# DC_DC.net
KiCad netlist of a schematic drawn in Altium Designer
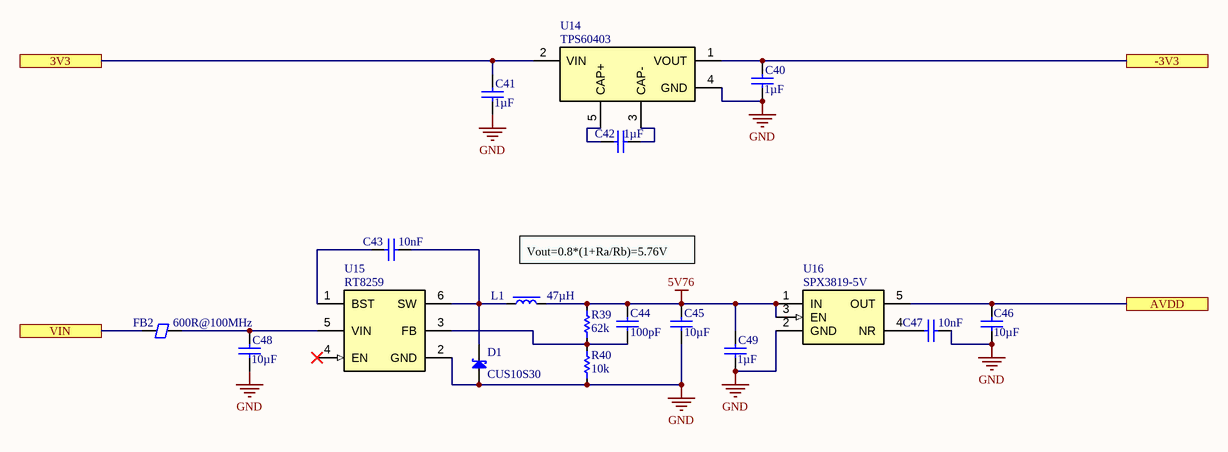
[diagram p0: DC DC.SchDoc]

(export (version "E")
  (design (tool "Eeschema 10.0.6"))
  (components
    (comp (ref "C40")
      (value "1µF")
      (footprint "CAP_CHIP_0603")
      (description "0603 Multilayer Ceramic Capacitors MLCC")
      (fields (field (name "PARTNUMBER") "CL10A105KB8NNNC") (field (name "TOLERANCE") "10%"))
      (libsource (lib "Sainsbury Wellcome Centre") (part "Cap"))
    )
    (comp (ref "C41")
      (value "1µF")
      (footprint "CAP_CHIP_0603")
      (description "0603 Multilayer Ceramic Capacitors MLCC")
      (fields (field (name "PARTNUMBER") "CL10A105KB8NNNC") (field (name "TOLERANCE") "10%"))
      (libsource (lib "Sainsbury Wellcome Centre") (part "Cap"))
    )
    (comp (ref "C42")
      (value "1µF")
      (footprint "CAP_CHIP_0603")
      (description "0603 Multilayer Ceramic Capacitors MLCC")
      (fields (field (name "PARTNUMBER") "CL10A105KB8NNNC") (field (name "TOLERANCE") "10%"))
      (libsource (lib "Sainsbury Wellcome Centre") (part "Cap"))
    )
    (comp (ref "C43")
      (value "10nF")
      (footprint "CAP_CHIP_0603")
      (description "0603 Multilayer Ceramic Capacitors MLCC")
      (fields (field (name "PARTNUMBER") "0603B103K500NT") (field (name "TOLERANCE") "10%"))
      (libsource (lib "Sainsbury Wellcome Centre") (part "Cap"))
    )
    (comp (ref "C44")
      (value "100pF")
      (footprint "CAP_CHIP_0603")
      (description "0603 Multilayer Ceramic Capacitors MLCC")
      (fields (field (name "TOLERANCE") "5%") (field (name "PARTNUMBER") "CL10C101JB8NNNC"))
      (libsource (lib "Sainsbury Wellcome Centre") (part "Cap"))
    )
    (comp (ref "C45")
      (value "10µF")
      (footprint "CAP_CHIP_0603")
      (fields
        (field (name "PARTNUMBER") "GRM188R6YA106MA73D")
        (field (name "TOLERANCE") "20%")
        (field (name "Comment") "C0603-10uF-35V")
      )
      (libsource (lib "Sainsbury Wellcome Centre") (part "Cap"))
    )
    (comp (ref "C46")
      (value "10µF")
      (footprint "CAP_CHIP_0603")
      (description "0603 Multilayer Ceramic Capacitors MLCC")
      (fields (field (name "PARTNUMBER") "CL10A106MA8NRNC") (field (name "TOLERANCE") "20%"))
      (libsource (lib "Sainsbury Wellcome Centre") (part "Cap"))
    )
    (comp (ref "C47")
      (value "10nF")
      (footprint "CAP_CHIP_0603")
      (description "0603 Multilayer Ceramic Capacitors MLCC")
      (fields (field (name "PARTNUMBER") "0603B103K500NT") (field (name "TOLERANCE") "10%"))
      (libsource (lib "Sainsbury Wellcome Centre") (part "Cap"))
    )
    (comp (ref "C48")
      (value "10µF")
      (footprint "CAP_CHIP_0603")
      (fields
        (field (name "PARTNUMBER") "GRM188R6YA106MA73D")
        (field (name "TOLERANCE") "20%")
        (field (name "Comment") "C0603-10uF-35V")
      )
      (libsource (lib "Sainsbury Wellcome Centre") (part "Cap"))
    )
    (comp (ref "C49")
      (value "1µF")
      (footprint "CAP_CHIP_0603")
      (description "0603 Multilayer Ceramic Capacitors MLCC")
      (fields (field (name "PARTNUMBER") "CL10A105KB8NNNC") (field (name "TOLERANCE") "10%"))
      (libsource (lib "Sainsbury Wellcome Centre") (part "Cap"))
    )
    (comp (ref "D1")
      (value "CUS10S30")
      (footprint "SOD323")
      (description "Rectifier Diode, Schottky, 1 Phase, 1 Element, 1A, 30V V(RRM), Silicon")
      (fields (field (name "PARTNUMBER") "CUS10S30,H3F"))
      (libsource (lib "Sainsbury Wellcome Centre") (part "Diode-Schottky"))
    )
    (comp (ref "FB2")
      (value "600R@100MHz")
      (footprint "FB_CHIP_0805")
      (description "Ferrite Chip, 1 Function(s), 0.5A, 2 Pin(s)")
      (fields (field (name "PARTNUMBER") "GZ2012D601TF") (field (name "Comment") "FB0805-600R-0.5A"))
      (libsource (lib "Sainsbury Wellcome Centre") (part "Bead"))
    )
    (comp (ref "L1")
      (value "47µH")
      (footprint "IND_PWR_1210")
      (description "Inductor Power Chip Shielded Wirewound 47uH 20% 1MHz Ferrite 0.5A 0.9Ohm DCR 1210 Automotive T/R")
      (fields (field (name "TOLERANCE") "20%") (field (name "PARTNUMBER") "LQW32FT470M0HL"))
      (libsource (lib "Sainsbury Wellcome Centre") (part "Inductor"))
    )
    (comp (ref "R39")
      (value "62k")
      (footprint "RES_CHIP_0603")
      (description "100mW Thick Film Resistors 75V ±100ppm/℃ ±1% 0603 Chip Resistor")
      (fields (field (name "TOLERANCE") "1%") (field (name "PARTNUMBER") "0603WAF6202T5E"))
      (libsource (lib "Sainsbury Wellcome Centre") (part "Res"))
    )
    (comp (ref "R40")
      (value "10k")
      (footprint "RES_CHIP_0603")
      (description "100mW Thick Film Resistors 75V ±100ppm/℃ ±1% 0603 Chip Resistor")
      (fields (field (name "PARTNUMBER") "0603WAF1002T5E") (field (name "TOLERANCE") "1%"))
      (libsource (lib "Sainsbury Wellcome Centre") (part "Res"))
    )
    (comp (ref "U14")
      (value "TPS60403")
      (footprint "SOT23-5")
      (description "60mA Charge Pump Voltage Inverter with Fixed 250kHz Operation 5-SOT-23 -40 to 85")
      (fields (field (name "PARTNUMBER") "TPS60403DBVR"))
      (libsource (lib "Sainsbury Wellcome Centre") (part "TPS60403"))
    )
    (comp (ref "U15")
      (value "RT8259")
      (footprint "SOT23-6")
      (description "Step-down type Adjustable 800mV~15V 1.2A 4.5V~24V Switching Regulator/Controller")
      (fields (field (name "PARTNUMBER") "RT8259GJ6"))
      (libsource (lib "Sainsbury Wellcome Centre") (part "RT8259"))
    )
    (comp (ref "U16")
      (value "SPX3819-5V")
      (footprint "SOT23-5")
      (description "500mA 70dB Fixed 3.3V Positive electrode 16V LDO")
      (fields (field (name "PARTNUMBER") "SPX3819M5-L-5-0/TR"))
      (libsource (lib "Sainsbury Wellcome Centre") (part "LDO-5P-NR"))
    )
  )
  (nets
    (net (code "1") (name "/-3V3") (class "Default")
      (node (ref "C40") (pin "1") (pinfunction "1_1") (pintype "passive"))
      (node (ref "U14") (pin "1") (pinfunction "VOUT_1") (pintype "power_in"))
    )
    (net (code "2") (name "/3V3") (class "Default")
      (node (ref "C41") (pin "1") (pinfunction "1_1") (pintype "passive"))
      (node (ref "U14") (pin "2") (pinfunction "VIN_2") (pintype "power_in"))
    )
    (net (code "3") (name "/AVDD") (class "Default")
      (node (ref "C46") (pin "2") (pinfunction "2_2") (pintype "passive"))
      (node (ref "U16") (pin "5") (pinfunction "OUT_5") (pintype "power_in"))
    )
    (net (code "4") (name "/VIN") (class "Default")
      (node (ref "FB2") (pin "1") (pinfunction "1_1") (pintype "passive"))
    )
    (net (code "5") (name "5V76") (class "Default")
      (node (ref "C44") (pin "2") (pinfunction "2_2") (pintype "passive"))
      (node (ref "C45") (pin "2") (pinfunction "2_2") (pintype "passive"))
      (node (ref "C49") (pin "1") (pinfunction "1_1") (pintype "passive"))
      (node (ref "L1") (pin "2") (pinfunction "2_2") (pintype "passive"))
      (node (ref "R39") (pin "2") (pinfunction "2_2") (pintype "passive"))
      (node (ref "U16") (pin "1") (pinfunction "IN_1") (pintype "power_in"))
      (node (ref "U16") (pin "3") (pinfunction "EN_3") (pintype "input"))
    )
    (net (code "6") (name "GND") (class "Default")
      (node (ref "C40") (pin "2") (pinfunction "2_2") (pintype "passive"))
      (node (ref "C41") (pin "2") (pinfunction "2_2") (pintype "passive"))
      (node (ref "C45") (pin "1") (pinfunction "1_1") (pintype "passive"))
      (node (ref "C46") (pin "1") (pinfunction "1_1") (pintype "passive"))
      (node (ref "C47") (pin "1") (pinfunction "1_1") (pintype "passive"))
      (node (ref "C48") (pin "1") (pinfunction "1_1") (pintype "passive"))
      (node (ref "C49") (pin "2") (pinfunction "2_2") (pintype "passive"))
      (node (ref "D1") (pin "2") (pinfunction "A_2") (pintype "passive"))
      (node (ref "R40") (pin "1") (pinfunction "1_1") (pintype "passive"))
      (node (ref "U14") (pin "4") (pinfunction "GND_4") (pintype "power_in"))
      (node (ref "U15") (pin "2") (pinfunction "GND_2") (pintype "power_in"))
      (node (ref "U16") (pin "2") (pinfunction "GND_2") (pintype "power_in"))
    )
    (net (code "7") (name "Net-(D1-C)") (class "Default")
      (node (ref "C43") (pin "1") (pinfunction "1_1") (pintype "passive"))
      (node (ref "D1") (pin "1") (pinfunction "C_1") (pintype "passive"))
      (node (ref "L1") (pin "1") (pinfunction "1_1") (pintype "passive"))
      (node (ref "U15") (pin "6") (pinfunction "SW_6") (pintype "passive"))
    )
    (net (code "8") (name "Net-(U14-CAP+)") (class "Default")
      (node (ref "C42") (pin "1") (pinfunction "1_1") (pintype "passive"))
      (node (ref "U14") (pin "5") (pinfunction "CAP+_5") (pintype "passive"))
    )
    (net (code "9") (name "Net-(U14-CAP-)") (class "Default")
      (node (ref "C42") (pin "2") (pinfunction "2_2") (pintype "passive"))
      (node (ref "U14") (pin "3") (pinfunction "CAP-_3") (pintype "passive"))
    )
    (net (code "10") (name "Net-(U15-BST)") (class "Default")
      (node (ref "C43") (pin "2") (pinfunction "2_2") (pintype "passive"))
      (node (ref "U15") (pin "1") (pinfunction "BST_1") (pintype "passive"))
    )
    (net (code "11") (name "Net-(U15-FB)") (class "Default")
      (node (ref "C44") (pin "1") (pinfunction "1_1") (pintype "passive"))
      (node (ref "R39") (pin "1") (pinfunction "1_1") (pintype "passive"))
      (node (ref "R40") (pin "2") (pinfunction "2_2") (pintype "passive"))
      (node (ref "U15") (pin "3") (pinfunction "FB_3") (pintype "passive"))
    )
    (net (code "12") (name "Net-(U15-VIN)") (class "Default")
      (node (ref "C48") (pin "2") (pinfunction "2_2") (pintype "passive"))
      (node (ref "FB2") (pin "2") (pinfunction "2_2") (pintype "passive"))
      (node (ref "U15") (pin "5") (pinfunction "VIN_5") (pintype "power_in"))
    )
    (net (code "13") (name "Net-(U16-NR)") (class "Default")
      (node (ref "C47") (pin "2") (pinfunction "2_2") (pintype "passive"))
      (node (ref "U16") (pin "4") (pinfunction "NR_4") (pintype "passive"))
    )
    (net (code "14") (name "unconnected-(U15-EN-Pad4)") (class "Default")
      (node (ref "U15") (pin "4") (pinfunction "EN_4") (pintype "input+no_connect"))
    )
  )
)
